# Sheet2_2.net
KiCad netlist of a schematic drawn in Altium Designer
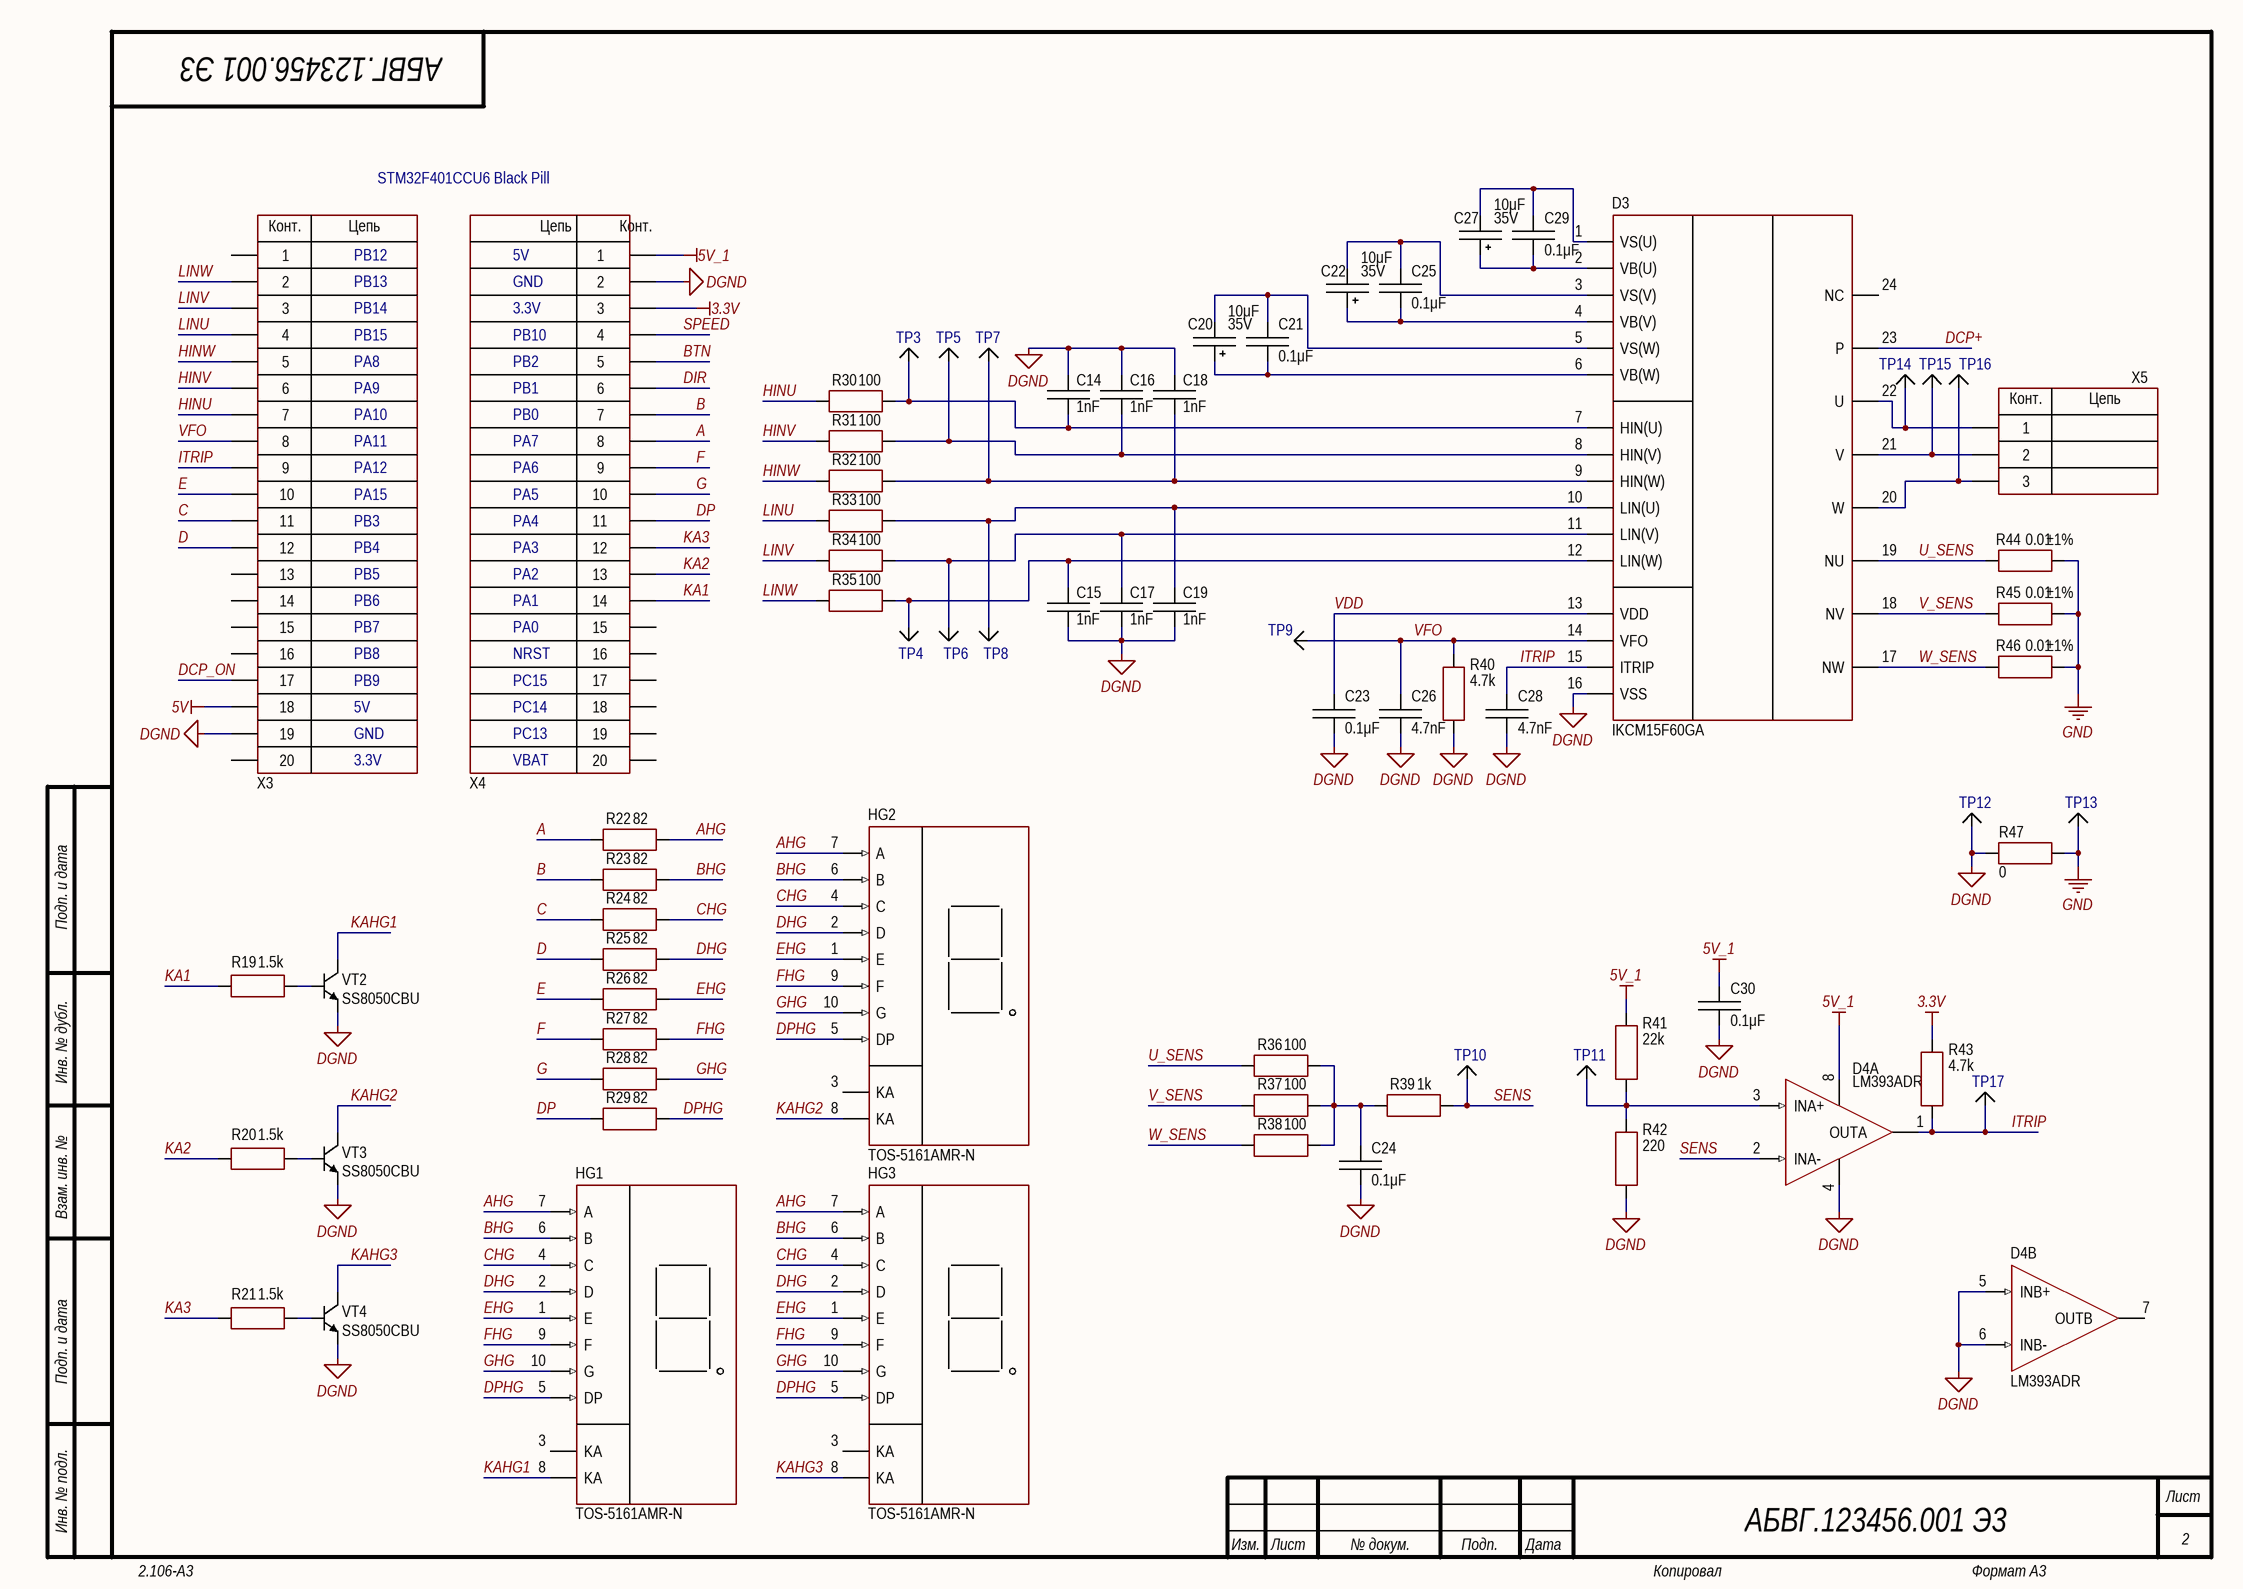
[diagram p0: Sheet2 (2).SchDoc]

(export (version "E")
  (design (tool "Eeschema 10.0.6"))
  (components
    (comp (ref "C14")
      (value "1nF")
      (footprint "CAP: 1206")
      (fields
        (field (name "PARTNUMBER") "Ceramic capacitor, 1nF,   50V")
        (field (name "VALUEMANUFACTURERPARTNUMBER") "Ceramic capacitor, 1nF, X7R, ±10%, 50V, 1206, -55...+125°C")
        (field (name "TOLERANCE") "±10%")
      )
      (libsource (lib "capacitor") (part "Ceramic_1206"))
    )
    (comp (ref "C15")
      (value "1nF")
      (footprint "CAP: 1206")
      (fields
        (field (name "PARTNUMBER") "Ceramic capacitor, 1nF,   50V")
        (field (name "VALUEMANUFACTURERPARTNUMBER") "Ceramic capacitor, 1nF, X7R, ±10%, 50V, 1206, -55...+125°C")
        (field (name "TOLERANCE") "±10%")
      )
      (libsource (lib "capacitor") (part "Ceramic_1206"))
    )
    (comp (ref "C16")
      (value "1nF")
      (footprint "CAP: 1206")
      (fields
        (field (name "PARTNUMBER") "Ceramic capacitor, 1nF,   50V")
        (field (name "VALUEMANUFACTURERPARTNUMBER") "Ceramic capacitor, 1nF, X7R, ±10%, 50V, 1206, -55...+125°C")
        (field (name "TOLERANCE") "±10%")
      )
      (libsource (lib "capacitor") (part "Ceramic_1206"))
    )
    (comp (ref "C17")
      (value "1nF")
      (footprint "CAP: 1206")
      (fields
        (field (name "PARTNUMBER") "Ceramic capacitor, 1nF,   50V")
        (field (name "VALUEMANUFACTURERPARTNUMBER") "Ceramic capacitor, 1nF, X7R, ±10%, 50V, 1206, -55...+125°C")
        (field (name "TOLERANCE") "±10%")
      )
      (libsource (lib "capacitor") (part "Ceramic_1206"))
    )
    (comp (ref "C18")
      (value "1nF")
      (footprint "CAP: 1206")
      (fields
        (field (name "PARTNUMBER") "Ceramic capacitor, 1nF,   50V")
        (field (name "VALUEMANUFACTURERPARTNUMBER") "Ceramic capacitor, 1nF, X7R, ±10%, 50V, 1206, -55...+125°C")
        (field (name "TOLERANCE") "±10%")
      )
      (libsource (lib "capacitor") (part "Ceramic_1206"))
    )
    (comp (ref "C19")
      (value "1nF")
      (footprint "CAP: 1206")
      (fields
        (field (name "PARTNUMBER") "Ceramic capacitor, 1nF,   50V")
        (field (name "VALUEMANUFACTURERPARTNUMBER") "Ceramic capacitor, 1nF, X7R, ±10%, 50V, 1206, -55...+125°C")
        (field (name "TOLERANCE") "±10%")
      )
      (libsource (lib "capacitor") (part "Ceramic_1206"))
    )
    (comp (ref "C20")
      (value "10μF")
      (footprint "CAP: D5C2H11")
      (fields
        (field (name "MANUFACTURER") "?")
        (field (name "PARTNUMBER") "9000565842")
        (field (name "VALUEMANUFACTURERPARTNUMBER") "Aluminium capacitor, 10μF, 35V, ±20%, 54mOhm, ?, -40...+105°C")
        (field (name "VOLTAGE") "35V")
      )
      (libsource (lib "capacitor") (part "Aluminium"))
    )
    (comp (ref "C21")
      (value "0.1μF")
      (footprint "CAP: 1206")
      (fields
        (field (name "PARTNUMBER") "Ceramic capacitor, 0.1μF,   50V")
        (field (name "VALUEMANUFACTURERPARTNUMBER") "Ceramic capacitor, 0.1μF, X7R, ±10%, 50V, 1206, -55...+125°C")
        (field (name "TOLERANCE") "±10%")
      )
      (libsource (lib "capacitor") (part "Ceramic_1206"))
    )
    (comp (ref "C22")
      (value "10μF")
      (footprint "CAP: D5C2H11")
      (fields
        (field (name "MANUFACTURER") "?")
        (field (name "PARTNUMBER") "9000565842")
        (field (name "VALUEMANUFACTURERPARTNUMBER") "Aluminium capacitor, 10μF, 35V, ±20%, 54mOhm, ?, -40...+105°C")
        (field (name "VOLTAGE") "35V")
      )
      (libsource (lib "capacitor") (part "Aluminium"))
    )
    (comp (ref "C23")
      (value "0.1μF")
      (footprint "CAP: 1206")
      (fields
        (field (name "PARTNUMBER") "Ceramic capacitor, 0.1μF,   50V")
        (field (name "VALUEMANUFACTURERPARTNUMBER") "Ceramic capacitor, 0.1μF, X7R, ±10%, 50V, 1206, -55...+125°C")
        (field (name "TOLERANCE") "±10%")
      )
      (libsource (lib "capacitor") (part "Ceramic_1206"))
    )
    (comp (ref "C24")
      (value "0.1μF")
      (footprint "CAP: 1206")
      (fields
        (field (name "PARTNUMBER") "Ceramic capacitor, 0.1μF,   50V")
        (field (name "VALUEMANUFACTURERPARTNUMBER") "Ceramic capacitor, 0.1μF, X7R, ±10%, 50V, 1206, -55...+125°C")
        (field (name "TOLERANCE") "±10%")
      )
      (libsource (lib "capacitor") (part "Ceramic_1206"))
    )
    (comp (ref "C25")
      (value "0.1μF")
      (footprint "CAP: 1206")
      (fields
        (field (name "PARTNUMBER") "Ceramic capacitor, 0.1μF,   50V")
        (field (name "VALUEMANUFACTURERPARTNUMBER") "Ceramic capacitor, 0.1μF, X7R, ±10%, 50V, 1206, -55...+125°C")
        (field (name "TOLERANCE") "±10%")
      )
      (libsource (lib "capacitor") (part "Ceramic_1206"))
    )
    (comp (ref "C26")
      (value "4.7nF")
      (footprint "CAP: 1206")
      (fields
        (field (name "PARTNUMBER") "Ceramic capacitor, 4.7nF,   50V")
        (field (name "VALUEMANUFACTURERPARTNUMBER") "Ceramic capacitor, 4.7nF, X7R, ±10%, 50V, 1206, -55...+125°C")
        (field (name "TOLERANCE") "±10%")
      )
      (libsource (lib "capacitor") (part "Ceramic_1206"))
    )
    (comp (ref "C27")
      (value "10μF")
      (footprint "CAP: D5C2H11")
      (fields
        (field (name "MANUFACTURER") "?")
        (field (name "PARTNUMBER") "9000565842")
        (field (name "VALUEMANUFACTURERPARTNUMBER") "Aluminium capacitor, 10μF, 35V, ±20%, 54mOhm, ?, -40...+105°C")
        (field (name "VOLTAGE") "35V")
      )
      (libsource (lib "capacitor") (part "Aluminium"))
    )
    (comp (ref "C28")
      (value "4.7nF")
      (footprint "CAP: 1206")
      (fields
        (field (name "PARTNUMBER") "Ceramic capacitor, 4.7nF,   50V")
        (field (name "VALUEMANUFACTURERPARTNUMBER") "Ceramic capacitor, 4.7nF, X7R, ±10%, 50V, 1206, -55...+125°C")
        (field (name "TOLERANCE") "±10%")
      )
      (libsource (lib "capacitor") (part "Ceramic_1206"))
    )
    (comp (ref "C29")
      (value "0.1μF")
      (footprint "CAP: 1206")
      (fields
        (field (name "PARTNUMBER") "Ceramic capacitor, 0.1μF,   50V")
        (field (name "VALUEMANUFACTURERPARTNUMBER") "Ceramic capacitor, 0.1μF, X7R, ±10%, 50V, 1206, -55...+125°C")
        (field (name "TOLERANCE") "±10%")
      )
      (libsource (lib "capacitor") (part "Ceramic_1206"))
    )
    (comp (ref "C30")
      (value "0.1μF")
      (footprint "CAP: 1206")
      (fields
        (field (name "PARTNUMBER") "Ceramic capacitor, 0.1μF,   50V")
        (field (name "VALUEMANUFACTURERPARTNUMBER") "Ceramic capacitor, 0.1μF, X7R, ±10%, 50V, 1206, -55...+125°C")
        (field (name "TOLERANCE") "±10%")
      )
      (libsource (lib "capacitor") (part "Ceramic_1206"))
    )
    (comp (ref "D3")
      (value "~")
      (footprint "INF-CIPOS MINI")
      (description "Fully isolated Dual In-Line molded  IGBT module")
      (fields
        (field (name "MANUFACTURER") "INFINEON TECHNOLOGIES AG.")
        (field (name "VALUEMANUFACTURERPARTNUMBER") "600 V, 15 A three-phase intelligent power module, , , 15A, , 450V, -40...+125°C, IKCM15F60GA")
        (field (name "PARTNUMBER") "IKCM15F60GA")
      )
      (libsource (lib "ic-power-module") (part "IKCM15F60GA"))
    )
    (comp (ref "D4")
      (value "~")
      (footprint "8-SOIC")
      (description "Low Power Low Offset Voltage Dual Comparator")
      (fields
        (field (name "MANUFACTURER") "UTD Semiconductor Co.,Ltd")
        (field (name "VALUEMANUFACTURERPARTNUMBER") "IC comparator, Rail-to-Rail, 2...36 V, ±1...±18 V, 0…70°C, SOP-8")
        (field (name "PARTNUMBER") "LM393ADR")
      )
      (libsource (lib "ic-comparator") (part "LM393ADR"))
    )
    (comp (ref "HG1")
      (value "~")
      (footprint "TOS-5161AMR-N")
      (description "Single Digit Display LED")
      (fields
        (field (name "MANUFACTURER") "Taiwan Oasis Technology Co., Ltd")
        (field (name "VALUEMANUFACTURERPARTNUMBER") "Single Digit Display LED, , -25...+85°C, TOS-5161AMR-N")
        (field (name "PARTNUMBER") "TOS-5161AMR-N")
      )
      (libsource (lib "indicator") (part "TOS-5161AMR-N"))
    )
    (comp (ref "HG2")
      (value "~")
      (footprint "TOS-5161AMR-N")
      (description "Single Digit Display LED")
      (fields
        (field (name "MANUFACTURER") "Taiwan Oasis Technology Co., Ltd")
        (field (name "VALUEMANUFACTURERPARTNUMBER") "Single Digit Display LED, , -25...+85°C, TOS-5161AMR-N")
        (field (name "PARTNUMBER") "TOS-5161AMR-N")
      )
      (libsource (lib "indicator") (part "TOS-5161AMR-N"))
    )
    (comp (ref "HG3")
      (value "~")
      (footprint "TOS-5161AMR-N")
      (description "Single Digit Display LED")
      (fields
        (field (name "MANUFACTURER") "Taiwan Oasis Technology Co., Ltd")
        (field (name "VALUEMANUFACTURERPARTNUMBER") "Single Digit Display LED, , -25...+85°C, TOS-5161AMR-N")
        (field (name "PARTNUMBER") "TOS-5161AMR-N")
      )
      (libsource (lib "indicator") (part "TOS-5161AMR-N"))
    )
    (comp (ref "R19")
      (value "1.5k")
      (footprint "RES: 1206")
      (fields
        (field (name "MANUFACTURER") "Yageo")
        (field (name "PARTNUMBER") "RC1206JR-07100RL")
        (field (name "VALUEMANUFACTURERPARTNUMBER") "Resistor film, 1.5k, ±5%, 1206, 0.25W, -55...+125°C")
      )
      (libsource (lib "resistor") (part "Resistor_1206"))
    )
    (comp (ref "R20")
      (value "1.5k")
      (footprint "RES: 1206")
      (fields
        (field (name "MANUFACTURER") "Yageo")
        (field (name "PARTNUMBER") "RC1206JR-07100RL")
        (field (name "VALUEMANUFACTURERPARTNUMBER") "Resistor film, 1.5k, ±5%, 1206, 0.25W, -55...+125°C")
      )
      (libsource (lib "resistor") (part "Resistor_1206"))
    )
    (comp (ref "R21")
      (value "1.5k")
      (footprint "RES: 1206")
      (fields
        (field (name "MANUFACTURER") "Yageo")
        (field (name "PARTNUMBER") "RC1206JR-07100RL")
        (field (name "VALUEMANUFACTURERPARTNUMBER") "Resistor film, 1.5k, ±5%, 1206, 0.25W, -55...+125°C")
      )
      (libsource (lib "resistor") (part "Resistor_1206"))
    )
    (comp (ref "R22")
      (value "82")
      (footprint "RES: 1206")
      (fields
        (field (name "MANUFACTURER") "Yageo")
        (field (name "PARTNUMBER") "RC1206JR-07100RL")
        (field (name "VALUEMANUFACTURERPARTNUMBER") "Resistor film, 82, ±5%, 1206, 0.25W, -55...+125°C")
      )
      (libsource (lib "resistor") (part "Resistor_1206"))
    )
    (comp (ref "R23")
      (value "82")
      (footprint "RES: 1206")
      (fields
        (field (name "MANUFACTURER") "Yageo")
        (field (name "PARTNUMBER") "RC1206JR-07100RL")
        (field (name "VALUEMANUFACTURERPARTNUMBER") "Resistor film, 82, ±5%, 1206, 0.25W, -55...+125°C")
      )
      (libsource (lib "resistor") (part "Resistor_1206"))
    )
    (comp (ref "R24")
      (value "82")
      (footprint "RES: 1206")
      (fields
        (field (name "MANUFACTURER") "Yageo")
        (field (name "PARTNUMBER") "RC1206JR-07100RL")
        (field (name "VALUEMANUFACTURERPARTNUMBER") "Resistor film, 82, ±5%, 1206, 0.25W, -55...+125°C")
      )
      (libsource (lib "resistor") (part "Resistor_1206"))
    )
    (comp (ref "R25")
      (value "82")
      (footprint "RES: 1206")
      (fields
        (field (name "MANUFACTURER") "Yageo")
        (field (name "PARTNUMBER") "RC1206JR-07100RL")
        (field (name "VALUEMANUFACTURERPARTNUMBER") "Resistor film, 82, ±5%, 1206, 0.25W, -55...+125°C")
      )
      (libsource (lib "resistor") (part "Resistor_1206"))
    )
    (comp (ref "R26")
      (value "82")
      (footprint "RES: 1206")
      (fields
        (field (name "MANUFACTURER") "Yageo")
        (field (name "PARTNUMBER") "RC1206JR-07100RL")
        (field (name "VALUEMANUFACTURERPARTNUMBER") "Resistor film, 82, ±5%, 1206, 0.25W, -55...+125°C")
      )
      (libsource (lib "resistor") (part "Resistor_1206"))
    )
    (comp (ref "R27")
      (value "82")
      (footprint "RES: 1206")
      (fields
        (field (name "MANUFACTURER") "Yageo")
        (field (name "PARTNUMBER") "RC1206JR-07100RL")
        (field (name "VALUEMANUFACTURERPARTNUMBER") "Resistor film, 82, ±5%, 1206, 0.25W, -55...+125°C")
      )
      (libsource (lib "resistor") (part "Resistor_1206"))
    )
    (comp (ref "R28")
      (value "82")
      (footprint "RES: 1206")
      (fields
        (field (name "MANUFACTURER") "Yageo")
        (field (name "PARTNUMBER") "RC1206JR-07100RL")
        (field (name "VALUEMANUFACTURERPARTNUMBER") "Resistor film, 82, ±5%, 1206, 0.25W, -55...+125°C")
      )
      (libsource (lib "resistor") (part "Resistor_1206"))
    )
    (comp (ref "R29")
      (value "82")
      (footprint "RES: 1206")
      (fields
        (field (name "MANUFACTURER") "Yageo")
        (field (name "PARTNUMBER") "RC1206JR-07100RL")
        (field (name "VALUEMANUFACTURERPARTNUMBER") "Resistor film, 82, ±5%, 1206, 0.25W, -55...+125°C")
      )
      (libsource (lib "resistor") (part "Resistor_1206"))
    )
    (comp (ref "R30")
      (value "100")
      (footprint "RES: 1206")
      (fields
        (field (name "MANUFACTURER") "Yageo")
        (field (name "PARTNUMBER") "RC1206JR-07100RL")
        (field (name "VALUEMANUFACTURERPARTNUMBER") "Resistor film, 100, ±5%, 1206, 0.25W, -55...+125°C")
      )
      (libsource (lib "resistor") (part "Resistor_1206"))
    )
    (comp (ref "R31")
      (value "100")
      (footprint "RES: 1206")
      (fields
        (field (name "MANUFACTURER") "Yageo")
        (field (name "PARTNUMBER") "RC1206JR-07100RL")
        (field (name "VALUEMANUFACTURERPARTNUMBER") "Resistor film, 100, ±5%, 1206, 0.25W, -55...+125°C")
      )
      (libsource (lib "resistor") (part "Resistor_1206"))
    )
    (comp (ref "R32")
      (value "100")
      (footprint "RES: 1206")
      (fields
        (field (name "MANUFACTURER") "Yageo")
        (field (name "PARTNUMBER") "RC1206JR-07100RL")
        (field (name "VALUEMANUFACTURERPARTNUMBER") "Resistor film, 100, ±5%, 1206, 0.25W, -55...+125°C")
      )
      (libsource (lib "resistor") (part "Resistor_1206"))
    )
    (comp (ref "R33")
      (value "100")
      (footprint "RES: 1206")
      (fields
        (field (name "MANUFACTURER") "Yageo")
        (field (name "PARTNUMBER") "RC1206JR-07100RL")
        (field (name "VALUEMANUFACTURERPARTNUMBER") "Resistor film, 100, ±5%, 1206, 0.25W, -55...+125°C")
      )
      (libsource (lib "resistor") (part "Resistor_1206"))
    )
    (comp (ref "R34")
      (value "100")
      (footprint "RES: 1206")
      (fields
        (field (name "MANUFACTURER") "Yageo")
        (field (name "PARTNUMBER") "RC1206JR-07100RL")
        (field (name "VALUEMANUFACTURERPARTNUMBER") "Resistor film, 100, ±5%, 1206, 0.25W, -55...+125°C")
      )
      (libsource (lib "resistor") (part "Resistor_1206"))
    )
    (comp (ref "R35")
      (value "100")
      (footprint "RES: 1206")
      (fields
        (field (name "MANUFACTURER") "Yageo")
        (field (name "PARTNUMBER") "RC1206JR-07100RL")
        (field (name "VALUEMANUFACTURERPARTNUMBER") "Resistor film, 100, ±5%, 1206, 0.25W, -55...+125°C")
      )
      (libsource (lib "resistor") (part "Resistor_1206"))
    )
    (comp (ref "R36")
      (value "100")
      (footprint "RES: 1206")
      (fields
        (field (name "MANUFACTURER") "Yageo")
        (field (name "PARTNUMBER") "RC1206JR-07100RL")
        (field (name "VALUEMANUFACTURERPARTNUMBER") "Resistor film, 100, ±5%, 1206, 0.25W, -55...+125°C")
      )
      (libsource (lib "resistor") (part "Resistor_1206"))
    )
    (comp (ref "R37")
      (value "100")
      (footprint "RES: 1206")
      (fields
        (field (name "MANUFACTURER") "Yageo")
        (field (name "PARTNUMBER") "RC1206JR-07100RL")
        (field (name "VALUEMANUFACTURERPARTNUMBER") "Resistor film, 100, ±5%, 1206, 0.25W, -55...+125°C")
      )
      (libsource (lib "resistor") (part "Resistor_1206"))
    )
    (comp (ref "R38")
      (value "100")
      (footprint "RES: 1206")
      (fields
        (field (name "MANUFACTURER") "Yageo")
        (field (name "PARTNUMBER") "RC1206JR-07100RL")
        (field (name "VALUEMANUFACTURERPARTNUMBER") "Resistor film, 100, ±5%, 1206, 0.25W, -55...+125°C")
      )
      (libsource (lib "resistor") (part "Resistor_1206"))
    )
    (comp (ref "R39")
      (value "1k")
      (footprint "RES: 1206")
      (fields
        (field (name "MANUFACTURER") "Yageo")
        (field (name "PARTNUMBER") "RC1206JR-07100RL")
        (field (name "VALUEMANUFACTURERPARTNUMBER") "Resistor film, 1k, ±5%, 1206, 0.25W, -55...+125°C")
      )
      (libsource (lib "resistor") (part "Resistor_1206"))
    )
    (comp (ref "R40")
      (value "4.7k")
      (footprint "RES: 1206")
      (fields
        (field (name "MANUFACTURER") "Yageo")
        (field (name "PARTNUMBER") "RC1206JR-07100RL")
        (field (name "VALUEMANUFACTURERPARTNUMBER") "Resistor film, 4.7k, ±5%, 1206, 0.25W, -55...+125°C")
      )
      (libsource (lib "") (part "Resistor_1206_1"))
    )
    (comp (ref "R41")
      (value "22k")
      (footprint "RES: 1206")
      (fields
        (field (name "MANUFACTURER") "Yageo")
        (field (name "PARTNUMBER") "RC1206JR-07100RL")
        (field (name "VALUEMANUFACTURERPARTNUMBER") "Resistor film, 22k, ±5%, 1206, 0.25W, -55...+125°C")
      )
      (libsource (lib "") (part "Resistor_1206_1"))
    )
    (comp (ref "R42")
      (value "220")
      (footprint "RES: 1206")
      (fields
        (field (name "MANUFACTURER") "Yageo")
        (field (name "PARTNUMBER") "RC1206JR-07100RL")
        (field (name "VALUEMANUFACTURERPARTNUMBER") "Resistor film, 220, ±5%, 1206, 0.25W, -55...+125°C")
      )
      (libsource (lib "") (part "Resistor_1206_1"))
    )
    (comp (ref "R43")
      (value "4.7k")
      (footprint "RES: 1206")
      (fields
        (field (name "MANUFACTURER") "Yageo")
        (field (name "PARTNUMBER") "RC1206JR-07100RL")
        (field (name "VALUEMANUFACTURERPARTNUMBER") "Resistor film, 4.7k, ±5%, 1206, 0.25W, -55...+125°C")
      )
      (libsource (lib "") (part "Resistor_1206_1"))
    )
    (comp (ref "R44")
      (value "0.01")
      (footprint "RES: 2512")
      (fields
        (field (name "MANUFACTURER") "UNI-ROYAL(Uniroyal Elec)")
        (field (name "PARTNUMBER") "25121WF100MT4E")
        (field (name "VALUEMANUFACTURERPARTNUMBER") "Resistor film, 0.01, ±1%, 2512, 1W, -55...+125°C")
        (field (name "TOLERANCE") "±1%")
      )
      (libsource (lib "resistor") (part "Resistor_2512"))
    )
    (comp (ref "R45")
      (value "0.01")
      (footprint "RES: 2512")
      (fields
        (field (name "MANUFACTURER") "UNI-ROYAL(Uniroyal Elec)")
        (field (name "PARTNUMBER") "25121WF100MT4E")
        (field (name "VALUEMANUFACTURERPARTNUMBER") "Resistor film, 0.01, ±1%, 2512, 1W, -55...+125°C")
        (field (name "TOLERANCE") "±1%")
      )
      (libsource (lib "resistor") (part "Resistor_2512"))
    )
    (comp (ref "R46")
      (value "0.01")
      (footprint "RES: 2512")
      (fields
        (field (name "MANUFACTURER") "UNI-ROYAL(Uniroyal Elec)")
        (field (name "PARTNUMBER") "25121WF100MT4E")
        (field (name "VALUEMANUFACTURERPARTNUMBER") "Resistor film, 0.01, ±1%, 2512, 1W, -55...+125°C")
        (field (name "TOLERANCE") "±1%")
      )
      (libsource (lib "resistor") (part "Resistor_2512"))
    )
    (comp (ref "R47")
      (value "0")
      (footprint "RES: 1206")
      (fields
        (field (name "MANUFACTURER") "Yageo")
        (field (name "PARTNUMBER") "RC1206JR-07100RL")
        (field (name "VALUEMANUFACTURERPARTNUMBER") "Resistor film, 0, ±5%, 1206, 0.25W, -55...+125°C")
      )
      (libsource (lib "") (part "Resistor_1206_2"))
    )
    (comp (ref "TP3")
      (value "Test_Point")
      (footprint "TEST POINT KEYSTONE")
      (libsource (lib "other") (part "Test_Point"))
    )
    (comp (ref "TP4")
      (value "Test_Point")
      (footprint "TEST POINT KEYSTONE")
      (libsource (lib "other") (part "Test_Point"))
    )
    (comp (ref "TP5")
      (value "Test_Point")
      (footprint "TEST POINT KEYSTONE")
      (libsource (lib "other") (part "Test_Point"))
    )
    (comp (ref "TP6")
      (value "Test_Point")
      (footprint "TEST POINT KEYSTONE")
      (libsource (lib "other") (part "Test_Point"))
    )
    (comp (ref "TP7")
      (value "Test_Point")
      (footprint "TEST POINT KEYSTONE")
      (libsource (lib "other") (part "Test_Point"))
    )
    (comp (ref "TP8")
      (value "Test_Point")
      (footprint "TEST POINT KEYSTONE")
      (libsource (lib "other") (part "Test_Point"))
    )
    (comp (ref "TP9")
      (value "Test_Point")
      (footprint "TEST POINT KEYSTONE")
      (libsource (lib "other") (part "Test_Point"))
    )
    (comp (ref "TP10")
      (value "Test_Point")
      (footprint "TEST POINT KEYSTONE")
      (libsource (lib "other") (part "Test_Point"))
    )
    (comp (ref "TP11")
      (value "Test_Point")
      (footprint "TEST POINT KEYSTONE")
      (libsource (lib "other") (part "Test_Point"))
    )
    (comp (ref "TP12")
      (value "Test_Point")
      (footprint "TEST POINT KEYSTONE")
      (libsource (lib "other") (part "Test_Point"))
    )
    (comp (ref "TP13")
      (value "Test_Point")
      (footprint "TEST POINT KEYSTONE")
      (libsource (lib "other") (part "Test_Point"))
    )
    (comp (ref "TP14")
      (value "Test_Point")
      (footprint "TEST POINT KEYSTONE")
      (libsource (lib "other") (part "Test_Point"))
    )
    (comp (ref "TP15")
      (value "Test_Point")
      (footprint "TEST POINT KEYSTONE")
      (libsource (lib "other") (part "Test_Point"))
    )
    (comp (ref "TP16")
      (value "Test_Point")
      (footprint "TEST POINT KEYSTONE")
      (libsource (lib "other") (part "Test_Point"))
    )
    (comp (ref "TP17")
      (value "Test_Point")
      (footprint "TEST POINT KEYSTONE")
      (libsource (lib "other") (part "Test_Point"))
    )
    (comp (ref "VT2")
      (value "~")
      (footprint "TO-92 - formed leads")
      (fields
        (field (name "MANUFACTURER") "ON Semiconductor")
        (field (name "VALUEMANUFACTURERPARTNUMBER") "NPN transistor, 40V, 1.5A, 190MHz, 1W, 0.5Vmax, 120...200, TO-92, 150°C")
        (field (name "PARTNUMBER") "SS8050CBU")
      )
      (libsource (lib "transistor") (part "SS8050CBU"))
    )
    (comp (ref "VT3")
      (value "~")
      (footprint "TO-92 - formed leads")
      (fields
        (field (name "MANUFACTURER") "ON Semiconductor")
        (field (name "VALUEMANUFACTURERPARTNUMBER") "NPN transistor, 40V, 1.5A, 190MHz, 1W, 0.5Vmax, 120...200, TO-92, 150°C")
        (field (name "PARTNUMBER") "SS8050CBU")
      )
      (libsource (lib "transistor") (part "SS8050CBU"))
    )
    (comp (ref "VT4")
      (value "~")
      (footprint "TO-92 - formed leads")
      (fields
        (field (name "MANUFACTURER") "ON Semiconductor")
        (field (name "VALUEMANUFACTURERPARTNUMBER") "NPN transistor, 40V, 1.5A, 190MHz, 1W, 0.5Vmax, 120...200, TO-92, 150°C")
        (field (name "PARTNUMBER") "SS8050CBU")
      )
      (libsource (lib "transistor") (part "SS8050CBU"))
    )
    (comp (ref "X3")
      (value "~")
      (footprint "PBS-20 narrow pitch")
      (fields
        (field (name "MANUFACTURER") "Connfly")
        (field (name "VALUEMANUFACTURERPARTNUMBER") "Connector, 20pin, 2.54mm, 500VAC, 3A")
        (field (name "PARTNUMBER") "PBS-20")
      )
      (libsource (lib "") (part "PBS-20_1"))
    )
    (comp (ref "X4")
      (value "~")
      (footprint "PBS-20 narrow pitch")
      (fields
        (field (name "MANUFACTURER") "Connfly")
        (field (name "VALUEMANUFACTURERPARTNUMBER") "Connector, 20pin, 2.54mm, 500VAC, 3A")
        (field (name "PARTNUMBER") "PBS-20")
      )
      (libsource (lib "connector") (part "PBS-20"))
    )
    (comp (ref "X5")
      (value "~")
      (footprint "DG128-7.5-03P")
      (fields
        (field (name "MANUFACTURER") "Degson Electronics")
        (field (name "VALUEMANUFACTURERPARTNUMBER") "Connector, 3pin, 9.53mm, 300VAC, 16A")
        (field (name "PARTNUMBER") "DG128-7.5-03P-14")
      )
      (libsource (lib "connector") (part "DG128-7.5-03P-14"))
    )
  )
  (nets
    (net (code "1") (name "/A") (class "Default")
      (node (ref "R22") (pin "1") (pinfunction "1_1") (pintype "passive"))
      (node (ref "X4") (pin "8") (pinfunction "8_8") (pintype "power_in"))
    )
    (net (code "2") (name "/AHG") (class "Default")
      (node (ref "HG1") (pin "7") (pinfunction "A_7") (pintype "input"))
      (node (ref "HG2") (pin "7") (pinfunction "A_7") (pintype "input"))
      (node (ref "HG3") (pin "7") (pinfunction "A_7") (pintype "input"))
      (node (ref "R22") (pin "2") (pinfunction "2_2") (pintype "passive"))
    )
    (net (code "3") (name "/B") (class "Default")
      (node (ref "R23") (pin "1") (pinfunction "1_1") (pintype "passive"))
      (node (ref "X4") (pin "7") (pinfunction "7_7") (pintype "power_in"))
    )
    (net (code "4") (name "/BHG") (class "Default")
      (node (ref "HG1") (pin "6") (pinfunction "B_6") (pintype "input"))
      (node (ref "HG2") (pin "6") (pinfunction "B_6") (pintype "input"))
      (node (ref "HG3") (pin "6") (pinfunction "B_6") (pintype "input"))
      (node (ref "R23") (pin "2") (pinfunction "2_2") (pintype "passive"))
    )
    (net (code "5") (name "/BTN") (class "Default")
      (node (ref "X4") (pin "5") (pinfunction "5_5") (pintype "power_in"))
    )
    (net (code "6") (name "/C") (class "Default")
      (node (ref "R24") (pin "1") (pinfunction "1_1") (pintype "passive"))
      (node (ref "X3") (pin "11") (pinfunction "11_11") (pintype "power_in"))
    )
    (net (code "7") (name "/CHG") (class "Default")
      (node (ref "HG1") (pin "4") (pinfunction "C_4") (pintype "input"))
      (node (ref "HG2") (pin "4") (pinfunction "C_4") (pintype "input"))
      (node (ref "HG3") (pin "4") (pinfunction "C_4") (pintype "input"))
      (node (ref "R24") (pin "2") (pinfunction "2_2") (pintype "passive"))
    )
    (net (code "8") (name "/D") (class "Default")
      (node (ref "R25") (pin "1") (pinfunction "1_1") (pintype "passive"))
      (node (ref "X3") (pin "12") (pinfunction "12_12") (pintype "power_in"))
    )
    (net (code "9") (name "/DCP+") (class "Default")
      (node (ref "D3") (pin "23") (pinfunction "P_23") (pintype "passive"))
    )
    (net (code "10") (name "/DCP_ON") (class "Default")
      (node (ref "X3") (pin "17") (pinfunction "17_17") (pintype "power_in"))
    )
    (net (code "11") (name "/DHG") (class "Default")
      (node (ref "HG1") (pin "2") (pinfunction "D_2") (pintype "input"))
      (node (ref "HG2") (pin "2") (pinfunction "D_2") (pintype "input"))
      (node (ref "HG3") (pin "2") (pinfunction "D_2") (pintype "input"))
      (node (ref "R25") (pin "2") (pinfunction "2_2") (pintype "passive"))
    )
    (net (code "12") (name "/DIR") (class "Default")
      (node (ref "X4") (pin "6") (pinfunction "6_6") (pintype "power_in"))
    )
    (net (code "13") (name "/DP") (class "Default")
      (node (ref "R29") (pin "1") (pinfunction "1_1") (pintype "passive"))
      (node (ref "X4") (pin "11") (pinfunction "11_11") (pintype "power_in"))
    )
    (net (code "14") (name "/DPHG") (class "Default")
      (node (ref "HG1") (pin "5") (pinfunction "DP_5") (pintype "input"))
      (node (ref "HG2") (pin "5") (pinfunction "DP_5") (pintype "input"))
      (node (ref "HG3") (pin "5") (pinfunction "DP_5") (pintype "input"))
      (node (ref "R29") (pin "2") (pinfunction "2_2") (pintype "passive"))
    )
    (net (code "15") (name "/E") (class "Default")
      (node (ref "R26") (pin "1") (pinfunction "1_1") (pintype "passive"))
      (node (ref "X3") (pin "10") (pinfunction "10_10") (pintype "power_in"))
    )
    (net (code "16") (name "/EHG") (class "Default")
      (node (ref "HG1") (pin "1") (pinfunction "E_1") (pintype "input"))
      (node (ref "HG2") (pin "1") (pinfunction "E_1") (pintype "input"))
      (node (ref "HG3") (pin "1") (pinfunction "E_1") (pintype "input"))
      (node (ref "R26") (pin "2") (pinfunction "2_2") (pintype "passive"))
    )
    (net (code "17") (name "/F") (class "Default")
      (node (ref "R27") (pin "1") (pinfunction "1_1") (pintype "passive"))
      (node (ref "X4") (pin "9") (pinfunction "9_9") (pintype "power_in"))
    )
    (net (code "18") (name "/FHG") (class "Default")
      (node (ref "HG1") (pin "9") (pinfunction "F_9") (pintype "input"))
      (node (ref "HG2") (pin "9") (pinfunction "F_9") (pintype "input"))
      (node (ref "HG3") (pin "9") (pinfunction "F_9") (pintype "input"))
      (node (ref "R27") (pin "2") (pinfunction "2_2") (pintype "passive"))
    )
    (net (code "19") (name "/G") (class "Default")
      (node (ref "R28") (pin "1") (pinfunction "1_1") (pintype "passive"))
      (node (ref "X4") (pin "10") (pinfunction "10_10") (pintype "power_in"))
    )
    (net (code "20") (name "/GHG") (class "Default")
      (node (ref "HG1") (pin "10") (pinfunction "G_10") (pintype "input"))
      (node (ref "HG2") (pin "10") (pinfunction "G_10") (pintype "input"))
      (node (ref "HG3") (pin "10") (pinfunction "G_10") (pintype "input"))
      (node (ref "R28") (pin "2") (pinfunction "2_2") (pintype "passive"))
    )
    (net (code "21") (name "/HINU") (class "Default")
      (node (ref "R30") (pin "1") (pinfunction "1_1") (pintype "passive"))
      (node (ref "X3") (pin "7") (pinfunction "7_7") (pintype "power_in"))
    )
    (net (code "22") (name "/HINV") (class "Default")
      (node (ref "R31") (pin "1") (pinfunction "1_1") (pintype "passive"))
      (node (ref "X3") (pin "6") (pinfunction "6_6") (pintype "power_in"))
    )
    (net (code "23") (name "/HINW") (class "Default")
      (node (ref "R32") (pin "1") (pinfunction "1_1") (pintype "passive"))
      (node (ref "X3") (pin "5") (pinfunction "5_5") (pintype "power_in"))
    )
    (net (code "24") (name "/ITRIP") (class "Default")
      (node (ref "C28") (pin "2") (pinfunction "2_2") (pintype "passive"))
      (node (ref "D3") (pin "15") (pinfunction "ITRIP_15") (pintype "passive"))
      (node (ref "D4") (pin "1") (pinfunction "OUTA_1") (pintype "power_in"))
      (node (ref "R43") (pin "1") (pinfunction "1_1") (pintype "passive"))
      (node (ref "TP17") (pin "1") (pinfunction "1_1") (pintype "passive"))
      (node (ref "X3") (pin "9") (pinfunction "9_9") (pintype "power_in"))
    )
    (net (code "25") (name "/KA1") (class "Default")
      (node (ref "R19") (pin "1") (pinfunction "1_1") (pintype "passive"))
      (node (ref "X4") (pin "14") (pinfunction "14_14") (pintype "power_in"))
    )
    (net (code "26") (name "/KA2") (class "Default")
      (node (ref "R20") (pin "1") (pinfunction "1_1") (pintype "passive"))
      (node (ref "X4") (pin "13") (pinfunction "13_13") (pintype "power_in"))
    )
    (net (code "27") (name "/KA3") (class "Default")
      (node (ref "R21") (pin "1") (pinfunction "1_1") (pintype "passive"))
      (node (ref "X4") (pin "12") (pinfunction "12_12") (pintype "power_in"))
    )
    (net (code "28") (name "/KAHG1") (class "Default")
      (node (ref "HG1") (pin "8") (pinfunction "KA_8") (pintype "passive"))
      (node (ref "VT2") (pin "3") (pinfunction "C_3") (pintype "passive"))
    )
    (net (code "29") (name "/KAHG2") (class "Default")
      (node (ref "HG2") (pin "8") (pinfunction "KA_8") (pintype "passive"))
      (node (ref "VT3") (pin "3") (pinfunction "C_3") (pintype "passive"))
    )
    (net (code "30") (name "/KAHG3") (class "Default")
      (node (ref "HG3") (pin "8") (pinfunction "KA_8") (pintype "passive"))
      (node (ref "VT4") (pin "3") (pinfunction "C_3") (pintype "passive"))
    )
    (net (code "31") (name "/LINU") (class "Default")
      (node (ref "R33") (pin "1") (pinfunction "1_1") (pintype "passive"))
      (node (ref "X3") (pin "4") (pinfunction "4_4") (pintype "power_in"))
    )
    (net (code "32") (name "/LINV") (class "Default")
      (node (ref "R34") (pin "1") (pinfunction "1_1") (pintype "passive"))
      (node (ref "X3") (pin "3") (pinfunction "3_3") (pintype "power_in"))
    )
    (net (code "33") (name "/LINW") (class "Default")
      (node (ref "R35") (pin "1") (pinfunction "1_1") (pintype "passive"))
      (node (ref "X3") (pin "2") (pinfunction "2_2") (pintype "passive"))
    )
    (net (code "34") (name "/SENS") (class "Default")
      (node (ref "D4") (pin "2") (pinfunction "INA-_2") (pintype "input"))
      (node (ref "R39") (pin "2") (pinfunction "2_2") (pintype "passive"))
      (node (ref "TP10") (pin "1") (pinfunction "1_1") (pintype "passive"))
    )
    (net (code "35") (name "/SPEED") (class "Default")
      (node (ref "X4") (pin "4") (pinfunction "4_4") (pintype "power_in"))
    )
    (net (code "36") (name "/U_SENS") (class "Default")
      (node (ref "D3") (pin "19") (pinfunction "NU_19") (pintype "passive"))
      (node (ref "R36") (pin "1") (pinfunction "1_1") (pintype "passive"))
      (node (ref "R44") (pin "1") (pinfunction "1_1") (pintype "passive"))
    )
    (net (code "37") (name "/VDD") (class "Default")
      (node (ref "C23") (pin "2") (pinfunction "2_2") (pintype "passive"))
      (node (ref "D3") (pin "13") (pinfunction "VDD_13") (pintype "passive"))
    )
    (net (code "38") (name "/VFO") (class "Default")
      (node (ref "C26") (pin "2") (pinfunction "2_2") (pintype "passive"))
      (node (ref "D3") (pin "14") (pinfunction "VFO_14") (pintype "passive"))
      (node (ref "R40") (pin "2") (pinfunction "2_2") (pintype "passive"))
      (node (ref "TP9") (pin "1") (pinfunction "1_1") (pintype "passive"))
      (node (ref "X3") (pin "8") (pinfunction "8_8") (pintype "power_in"))
    )
    (net (code "39") (name "/V_SENS") (class "Default")
      (node (ref "D3") (pin "18") (pinfunction "NV_18") (pintype "passive"))
      (node (ref "R37") (pin "1") (pinfunction "1_1") (pintype "passive"))
      (node (ref "R45") (pin "1") (pinfunction "1_1") (pintype "passive"))
    )
    (net (code "40") (name "/W_SENS") (class "Default")
      (node (ref "D3") (pin "17") (pinfunction "NW_17") (pintype "passive"))
      (node (ref "R38") (pin "1") (pinfunction "1_1") (pintype "passive"))
      (node (ref "R46") (pin "1") (pinfunction "1_1") (pintype "passive"))
    )
    (net (code "41") (name "3.3V") (class "Default")
      (node (ref "R43") (pin "2") (pinfunction "2_2") (pintype "passive"))
      (node (ref "X4") (pin "3") (pinfunction "3_3") (pintype "power_in"))
    )
    (net (code "42") (name "5V") (class "Default")
      (node (ref "X3") (pin "18") (pinfunction "18_18") (pintype "power_in"))
    )
    (net (code "43") (name "5V_1") (class "Default")
      (node (ref "C30") (pin "2") (pinfunction "2_2") (pintype "passive"))
      (node (ref "D4") (pin "8") (pinfunction "V+_8") (pintype "power_in"))
      (node (ref "R41") (pin "2") (pinfunction "2_2") (pintype "passive"))
      (node (ref "X4") (pin "1") (pinfunction "1_1") (pintype "passive"))
    )
    (net (code "44") (name "DGND") (class "Default")
      (node (ref "C14") (pin "2") (pinfunction "2_2") (pintype "passive"))
      (node (ref "C15") (pin "1") (pinfunction "1_1") (pintype "passive"))
      (node (ref "C16") (pin "2") (pinfunction "2_2") (pintype "passive"))
      (node (ref "C17") (pin "1") (pinfunction "1_1") (pintype "passive"))
      (node (ref "C18") (pin "2") (pinfunction "2_2") (pintype "passive"))
      (node (ref "C19") (pin "1") (pinfunction "1_1") (pintype "passive"))
      (node (ref "C23") (pin "1") (pinfunction "1_1") (pintype "passive"))
      (node (ref "C24") (pin "1") (pinfunction "1_1") (pintype "passive"))
      (node (ref "C26") (pin "1") (pinfunction "1_1") (pintype "passive"))
      (node (ref "C28") (pin "1") (pinfunction "1_1") (pintype "passive"))
      (node (ref "C30") (pin "1") (pinfunction "1_1") (pintype "passive"))
      (node (ref "D3") (pin "16") (pinfunction "VSS_16") (pintype "passive"))
      (node (ref "D4") (pin "4") (pinfunction "GND_4") (pintype "power_in"))
      (node (ref "D4") (pin "5") (pinfunction "INB+_5") (pintype "input"))
      (node (ref "D4") (pin "6") (pinfunction "INB-_6") (pintype "input"))
      (node (ref "R40") (pin "1") (pinfunction "1_1") (pintype "passive"))
      (node (ref "R42") (pin "1") (pinfunction "1_1") (pintype "passive"))
      (node (ref "R47") (pin "2") (pinfunction "2_2") (pintype "passive"))
      (node (ref "TP12") (pin "1") (pinfunction "1_1") (pintype "passive"))
      (node (ref "VT2") (pin "1") (pinfunction "E_1") (pintype "passive"))
      (node (ref "VT3") (pin "1") (pinfunction "E_1") (pintype "passive"))
      (node (ref "VT4") (pin "1") (pinfunction "E_1") (pintype "passive"))
      (node (ref "X3") (pin "19") (pinfunction "19_19") (pintype "power_in"))
      (node (ref "X4") (pin "2") (pinfunction "2_2") (pintype "passive"))
    )
    (net (code "45") (name "GND") (class "Default")
      (node (ref "R44") (pin "2") (pinfunction "2_2") (pintype "passive"))
      (node (ref "R45") (pin "2") (pinfunction "2_2") (pintype "passive"))
      (node (ref "R46") (pin "2") (pinfunction "2_2") (pintype "passive"))
      (node (ref "R47") (pin "1") (pinfunction "1_1") (pintype "passive"))
      (node (ref "TP13") (pin "1") (pinfunction "1_1") (pintype "passive"))
    )
    (net (code "46") (name "Net-(C24-Pad2)") (class "Default")
      (node (ref "C24") (pin "2") (pinfunction "2_2") (pintype "passive"))
      (node (ref "R36") (pin "2") (pinfunction "2_2") (pintype "passive"))
      (node (ref "R37") (pin "2") (pinfunction "2_2") (pintype "passive"))
      (node (ref "R38") (pin "2") (pinfunction "2_2") (pintype "passive"))
      (node (ref "R39") (pin "1") (pinfunction "1_1") (pintype "passive"))
    )
    (net (code "47") (name "Net-(D3-HIN(U))") (class "Default")
      (node (ref "C14") (pin "1") (pinfunction "1_1") (pintype "passive"))
      (node (ref "D3") (pin "7") (pinfunction "HIN(U)_7") (pintype "passive"))
      (node (ref "R30") (pin "2") (pinfunction "2_2") (pintype "passive"))
      (node (ref "TP3") (pin "1") (pinfunction "1_1") (pintype "passive"))
    )
    (net (code "48") (name "Net-(D3-HIN(V))") (class "Default")
      (node (ref "C16") (pin "1") (pinfunction "1_1") (pintype "passive"))
      (node (ref "D3") (pin "8") (pinfunction "HIN(V)_8") (pintype "passive"))
      (node (ref "R31") (pin "2") (pinfunction "2_2") (pintype "passive"))
      (node (ref "TP5") (pin "1") (pinfunction "1_1") (pintype "passive"))
    )
    (net (code "49") (name "Net-(D3-HIN(W))") (class "Default")
      (node (ref "C18") (pin "1") (pinfunction "1_1") (pintype "passive"))
      (node (ref "D3") (pin "9") (pinfunction "HIN(W)_9") (pintype "passive"))
      (node (ref "R32") (pin "2") (pinfunction "2_2") (pintype "passive"))
      (node (ref "TP7") (pin "1") (pinfunction "1_1") (pintype "passive"))
    )
    (net (code "50") (name "Net-(D3-LIN(U))") (class "Default")
      (node (ref "C19") (pin "2") (pinfunction "2_2") (pintype "passive"))
      (node (ref "D3") (pin "10") (pinfunction "LIN(U)_10") (pintype "passive"))
      (node (ref "R33") (pin "2") (pinfunction "2_2") (pintype "passive"))
      (node (ref "TP8") (pin "1") (pinfunction "1_1") (pintype "passive"))
    )
    (net (code "51") (name "Net-(D3-LIN(V))") (class "Default")
      (node (ref "C17") (pin "2") (pinfunction "2_2") (pintype "passive"))
      (node (ref "D3") (pin "11") (pinfunction "LIN(V)_11") (pintype "passive"))
      (node (ref "R34") (pin "2") (pinfunction "2_2") (pintype "passive"))
      (node (ref "TP6") (pin "1") (pinfunction "1_1") (pintype "passive"))
    )
    (net (code "52") (name "Net-(D3-LIN(W))") (class "Default")
      (node (ref "C15") (pin "2") (pinfunction "2_2") (pintype "passive"))
      (node (ref "D3") (pin "12") (pinfunction "LIN(W)_12") (pintype "passive"))
      (node (ref "R35") (pin "2") (pinfunction "2_2") (pintype "passive"))
      (node (ref "TP4") (pin "1") (pinfunction "1_1") (pintype "passive"))
    )
    (net (code "53") (name "Net-(D3-U)") (class "Default")
      (node (ref "D3") (pin "22") (pinfunction "U_22") (pintype "passive"))
      (node (ref "TP14") (pin "1") (pinfunction "1_1") (pintype "passive"))
      (node (ref "X5") (pin "1") (pinfunction "1_1") (pintype "passive"))
    )
    (net (code "54") (name "Net-(D3-V)") (class "Default")
      (node (ref "D3") (pin "21") (pinfunction "V_21") (pintype "passive"))
      (node (ref "TP15") (pin "1") (pinfunction "1_1") (pintype "passive"))
      (node (ref "X5") (pin "2") (pinfunction "2_2") (pintype "passive"))
    )
    (net (code "55") (name "Net-(D3-VB(U))") (class "Default")
      (node (ref "C27") (pin "1") (pinfunction "1_1") (pintype "passive"))
      (node (ref "C29") (pin "1") (pinfunction "1_1") (pintype "passive"))
      (node (ref "D3") (pin "2") (pinfunction "VB(U)_2") (pintype "passive"))
    )
    (net (code "56") (name "Net-(D3-VB(V))") (class "Default")
      (node (ref "C22") (pin "1") (pinfunction "1_1") (pintype "passive"))
      (node (ref "C25") (pin "1") (pinfunction "1_1") (pintype "passive"))
      (node (ref "D3") (pin "4") (pinfunction "VB(V)_4") (pintype "passive"))
    )
    (net (code "57") (name "Net-(D3-VB(W))") (class "Default")
      (node (ref "C20") (pin "1") (pinfunction "1_1") (pintype "passive"))
      (node (ref "C21") (pin "1") (pinfunction "1_1") (pintype "passive"))
      (node (ref "D3") (pin "6") (pinfunction "VB(W)_6") (pintype "passive"))
    )
    (net (code "58") (name "Net-(D3-VS(U))") (class "Default")
      (node (ref "C27") (pin "2") (pinfunction "2_2") (pintype "passive"))
      (node (ref "C29") (pin "2") (pinfunction "2_2") (pintype "passive"))
      (node (ref "D3") (pin "1") (pinfunction "VS(U)_1") (pintype "passive"))
    )
    (net (code "59") (name "Net-(D3-VS(V))") (class "Default")
      (node (ref "C22") (pin "2") (pinfunction "2_2") (pintype "passive"))
      (node (ref "C25") (pin "2") (pinfunction "2_2") (pintype "passive"))
      (node (ref "D3") (pin "3") (pinfunction "VS(V)_3") (pintype "passive"))
    )
    (net (code "60") (name "Net-(D3-VS(W))") (class "Default")
      (node (ref "C20") (pin "2") (pinfunction "2_2") (pintype "passive"))
      (node (ref "C21") (pin "2") (pinfunction "2_2") (pintype "passive"))
      (node (ref "D3") (pin "5") (pinfunction "VS(W)_5") (pintype "passive"))
    )
    (net (code "61") (name "Net-(D3-W)") (class "Default")
      (node (ref "D3") (pin "20") (pinfunction "W_20") (pintype "passive"))
      (node (ref "TP16") (pin "1") (pinfunction "1_1") (pintype "passive"))
      (node (ref "X5") (pin "3") (pinfunction "3_3") (pintype "passive"))
    )
    (net (code "62") (name "Net-(D4A-INA+)") (class "Default")
      (node (ref "D4") (pin "3") (pinfunction "INA+_3") (pintype "input"))
      (node (ref "R41") (pin "1") (pinfunction "1_1") (pintype "passive"))
      (node (ref "R42") (pin "2") (pinfunction "2_2") (pintype "passive"))
      (node (ref "TP11") (pin "1") (pinfunction "1_1") (pintype "passive"))
    )
    (net (code "63") (name "Net-(VT2-B)") (class "Default")
      (node (ref "R19") (pin "2") (pinfunction "2_2") (pintype "passive"))
      (node (ref "VT2") (pin "2") (pinfunction "B_2") (pintype "passive"))
    )
    (net (code "64") (name "Net-(VT3-B)") (class "Default")
      (node (ref "R20") (pin "2") (pinfunction "2_2") (pintype "passive"))
      (node (ref "VT3") (pin "2") (pinfunction "B_2") (pintype "passive"))
    )
    (net (code "65") (name "Net-(VT4-B)") (class "Default")
      (node (ref "R21") (pin "2") (pinfunction "2_2") (pintype "passive"))
      (node (ref "VT4") (pin "2") (pinfunction "B_2") (pintype "passive"))
    )
    (net (code "66") (name "unconnected-(D3-NC-Pad24)") (class "Default")
      (node (ref "D3") (pin "24") (pinfunction "NC_24") (pintype "passive"))
    )
    (net (code "67") (name "unconnected-(D4B-OUTB-Pad7)") (class "Default")
      (node (ref "D4") (pin "7") (pinfunction "OUTB_7") (pintype "power_in"))
    )
    (net (code "68") (name "unconnected-(HG1-KA-Pad3)") (class "Default")
      (node (ref "HG1") (pin "3") (pinfunction "KA_3") (pintype "passive"))
    )
    (net (code "69") (name "unconnected-(HG2-KA-Pad3)") (class "Default")
      (node (ref "HG2") (pin "3") (pinfunction "KA_3") (pintype "passive"))
    )
    (net (code "70") (name "unconnected-(HG3-KA-Pad3)") (class "Default")
      (node (ref "HG3") (pin "3") (pinfunction "KA_3") (pintype "passive"))
    )
    (net (code "71") (name "unconnected-(X3-Pad1)") (class "Default")
      (node (ref "X3") (pin "1") (pinfunction "1_1") (pintype "passive"))
    )
    (net (code "72") (name "unconnected-(X3-Pad13)") (class "Default")
      (node (ref "X3") (pin "13") (pinfunction "13_13") (pintype "power_in"))
    )
    (net (code "73") (name "unconnected-(X3-Pad14)") (class "Default")
      (node (ref "X3") (pin "14") (pinfunction "14_14") (pintype "power_in"))
    )
    (net (code "74") (name "unconnected-(X3-Pad15)") (class "Default")
      (node (ref "X3") (pin "15") (pinfunction "15_15") (pintype "power_in"))
    )
    (net (code "75") (name "unconnected-(X3-Pad16)") (class "Default")
      (node (ref "X3") (pin "16") (pinfunction "16_16") (pintype "power_in"))
    )
    (net (code "76") (name "unconnected-(X3-Pad20)") (class "Default")
      (node (ref "X3") (pin "20") (pinfunction "20_20") (pintype "power_in"))
    )
    (net (code "77") (name "unconnected-(X4-Pad15)") (class "Default")
      (node (ref "X4") (pin "15") (pinfunction "15_15") (pintype "power_in"))
    )
    (net (code "78") (name "unconnected-(X4-Pad16)") (class "Default")
      (node (ref "X4") (pin "16") (pinfunction "16_16") (pintype "power_in"))
    )
    (net (code "79") (name "unconnected-(X4-Pad17)") (class "Default")
      (node (ref "X4") (pin "17") (pinfunction "17_17") (pintype "power_in"))
    )
    (net (code "80") (name "unconnected-(X4-Pad18)") (class "Default")
      (node (ref "X4") (pin "18") (pinfunction "18_18") (pintype "power_in"))
    )
    (net (code "81") (name "unconnected-(X4-Pad19)") (class "Default")
      (node (ref "X4") (pin "19") (pinfunction "19_19") (pintype "power_in"))
    )
    (net (code "82") (name "unconnected-(X4-Pad20)") (class "Default")
      (node (ref "X4") (pin "20") (pinfunction "20_20") (pintype "power_in"))
    )
  )
)
